# Spica_1_1.net
KiCad netlist of a schematic drawn in EAGLE
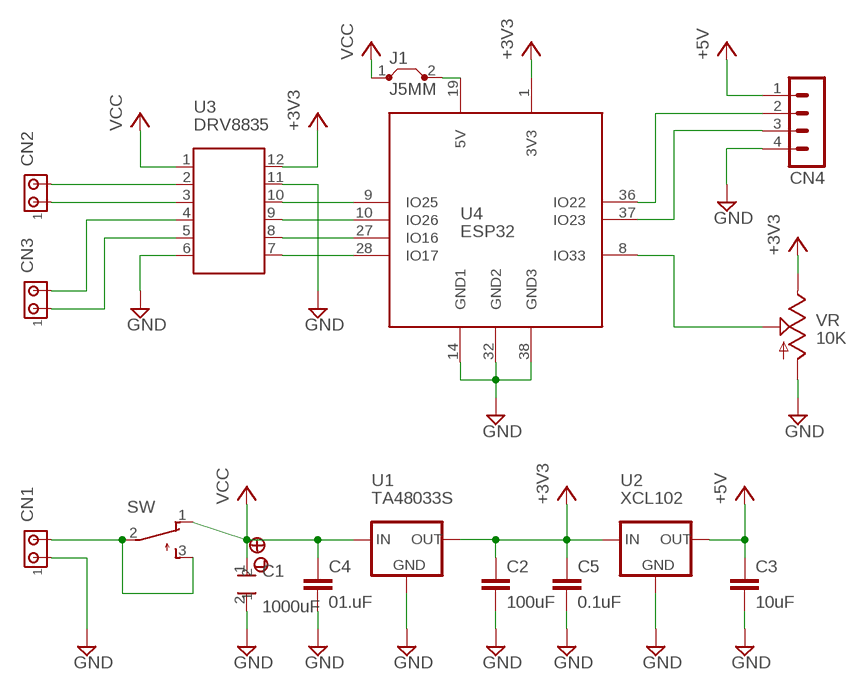
[diagram p0: schematic, sheet 1]

(export (version "E")
  (design (tool "Eeschema 10.0.6"))
  (components
    (comp (ref "C1")
      (value "1000uF")
      (footprint "eagle-import:ELECTROLYTIC_CAPACITOR_LARGE")
      (libsource (lib "eagle-import") (part "ELECTROLYTIC_CAPACITOR_LARGE"))
    )
    (comp (ref "C2")
      (value "100uF")
      (footprint "eagle-import:C2.5-5")
      (libsource (lib "eagle-import") (part "C2.5/5"))
    )
    (comp (ref "C3")
      (value "10uF")
      (footprint "eagle-import:C2.5-5")
      (libsource (lib "eagle-import") (part "C2.5/5"))
    )
    (comp (ref "C4")
      (value "01.uF")
      (footprint "eagle-import:C2.5-2")
      (libsource (lib "eagle-import") (part "C2.5/2"))
    )
    (comp (ref "C5")
      (value "0.1uF")
      (footprint "eagle-import:C2.5-2")
      (libsource (lib "eagle-import") (part "C2.5/2"))
    )
    (comp (ref "CN1")
      (value "MTA02-100")
      (footprint "eagle-import:10X02MTA")
      (libsource (lib "eagle-import") (part "MTA02-100"))
    )
    (comp (ref "CN2")
      (value "MTA02-100")
      (footprint "eagle-import:10X02MTA")
      (libsource (lib "eagle-import") (part "MTA02-100"))
    )
    (comp (ref "CN3")
      (value "MTA02-100")
      (footprint "eagle-import:10X02MTA")
      (libsource (lib "eagle-import") (part "MTA02-100"))
    )
    (comp (ref "CN4")
      (value "MA04-1")
      (footprint "eagle-import:MA04-1")
      (libsource (lib "eagle-import") (part "MA04-1"))
    )
    (comp (ref "J1")
      (value "J5MM")
      (footprint "eagle-import:05")
      (libsource (lib "eagle-import") (part "J5MM"))
    )
    (comp (ref "SW")
      (value "TL32PO")
      (footprint "eagle-import:TL3XPO")
      (libsource (lib "eagle-import") (part "TL32PO"))
    )
    (comp (ref "U1")
      (value "TA48033S")
      (footprint "eagle-import:78XXS")
      (libsource (lib "eagle-import") (part "78XXS"))
    )
    (comp (ref "U2")
      (value "XCL102")
      (footprint "eagle-import:78XXS")
      (libsource (lib "eagle-import") (part "78XXS"))
    )
    (comp (ref "U3")
      (value "DRV8835")
      (footprint "eagle-import:DRV8835")
      (libsource (lib "eagle-import") (part "DRV8835"))
    )
    (comp (ref "U4")
      (value "ESP32")
      (footprint "eagle-import:ESP32")
      (libsource (lib "eagle-import") (part "ESP32"))
    )
    (comp (ref "VR")
      (value "10K")
      (footprint "eagle-import:CA6V")
      (libsource (lib "eagle-import") (part "TRIM_US-CA6V"))
    )
  )
  (nets
    (net (code "1") (name "+3V3") (class "Default")
      (node (ref "C2") (pin "1") (pinfunction "1_1") (pintype "passive"))
      (node (ref "C5") (pin "1") (pinfunction "1_1") (pintype "passive"))
      (node (ref "U1") (pin "OUT") (pinfunction "OUT_OUT") (pintype "passive"))
      (node (ref "U2") (pin "IN") (pinfunction "IN_IN") (pintype "input"))
      (node (ref "U3") (pin "12") (pinfunction "12_12") (pintype "bidirectional"))
      (node (ref "U4") (pin "1") (pinfunction "3V3_1") (pintype "bidirectional"))
      (node (ref "VR") (pin "E") (pinfunction "E_E") (pintype "passive"))
    )
    (net (code "2") (name "+5V") (class "Default")
      (node (ref "C3") (pin "1") (pinfunction "1_1") (pintype "passive"))
      (node (ref "CN4") (pin "1") (pinfunction "1_1") (pintype "passive"))
      (node (ref "U2") (pin "OUT") (pinfunction "OUT_OUT") (pintype "passive"))
    )
    (net (code "3") (name "GND") (class "Default")
      (node (ref "C1") (pin "2") (pinfunction "2_2") (pintype "bidirectional"))
      (node (ref "C2") (pin "2") (pinfunction "2_2") (pintype "passive"))
      (node (ref "C3") (pin "2") (pinfunction "2_2") (pintype "passive"))
      (node (ref "C4") (pin "2") (pinfunction "2_2") (pintype "passive"))
      (node (ref "C5") (pin "2") (pinfunction "2_2") (pintype "passive"))
      (node (ref "CN1") (pin "1") (pinfunction "1_1") (pintype "passive"))
      (node (ref "CN4") (pin "4") (pinfunction "4_4") (pintype "passive"))
      (node (ref "U1") (pin "GND") (pinfunction "GND_GND") (pintype "input"))
      (node (ref "U2") (pin "GND") (pinfunction "GND_GND") (pintype "input"))
      (node (ref "U3") (pin "11") (pinfunction "11_11") (pintype "bidirectional"))
      (node (ref "U3") (pin "6") (pinfunction "6_6") (pintype "bidirectional"))
      (node (ref "U4") (pin "14") (pinfunction "GND1_14") (pintype "bidirectional"))
      (node (ref "U4") (pin "32") (pinfunction "GND2_32") (pintype "bidirectional"))
      (node (ref "U4") (pin "38") (pinfunction "GND3_38") (pintype "bidirectional"))
      (node (ref "VR") (pin "A") (pinfunction "A_A") (pintype "passive"))
    )
    (net (code "4") (name "Net-(CN2-Pad1)") (class "Default")
      (node (ref "CN2") (pin "1") (pinfunction "1_1") (pintype "passive"))
      (node (ref "U3") (pin "3") (pinfunction "3_3") (pintype "bidirectional"))
    )
    (net (code "5") (name "Net-(CN2-Pad2)") (class "Default")
      (node (ref "CN2") (pin "2") (pinfunction "2_2") (pintype "passive"))
      (node (ref "U3") (pin "2") (pinfunction "2_2") (pintype "bidirectional"))
    )
    (net (code "6") (name "Net-(CN3-Pad1)") (class "Default")
      (node (ref "CN3") (pin "1") (pinfunction "1_1") (pintype "passive"))
      (node (ref "U3") (pin "5") (pinfunction "5_5") (pintype "bidirectional"))
    )
    (net (code "7") (name "Net-(CN3-Pad2)") (class "Default")
      (node (ref "CN3") (pin "2") (pinfunction "2_2") (pintype "passive"))
      (node (ref "U3") (pin "4") (pinfunction "4_4") (pintype "bidirectional"))
    )
    (net (code "8") (name "Net-(SW-P)") (class "Default")
      (node (ref "CN1") (pin "2") (pinfunction "2_2") (pintype "passive"))
      (node (ref "SW") (pin "2") (pinfunction "P_2") (pintype "passive"))
      (node (ref "SW") (pin "3") (pinfunction "S_3") (pintype "passive"))
    )
    (net (code "9") (name "Net-(U4-5V)") (class "Default")
      (node (ref "J1") (pin "2") (pinfunction "2_2") (pintype "passive"))
      (node (ref "U4") (pin "19") (pinfunction "5V_19") (pintype "bidirectional"))
    )
    (net (code "10") (name "Net-(U4-IO16)") (class "Default")
      (node (ref "U3") (pin "8") (pinfunction "8_8") (pintype "bidirectional"))
      (node (ref "U4") (pin "27") (pinfunction "IO16_27") (pintype "bidirectional"))
    )
    (net (code "11") (name "Net-(U4-IO17)") (class "Default")
      (node (ref "U3") (pin "7") (pinfunction "7_7") (pintype "bidirectional"))
      (node (ref "U4") (pin "28") (pinfunction "IO17_28") (pintype "bidirectional"))
    )
    (net (code "12") (name "Net-(U4-IO22)") (class "Default")
      (node (ref "CN4") (pin "2") (pinfunction "2_2") (pintype "passive"))
      (node (ref "U4") (pin "36") (pinfunction "IO22_36") (pintype "bidirectional"))
    )
    (net (code "13") (name "Net-(U4-IO23)") (class "Default")
      (node (ref "CN4") (pin "3") (pinfunction "3_3") (pintype "passive"))
      (node (ref "U4") (pin "37") (pinfunction "IO23_37") (pintype "bidirectional"))
    )
    (net (code "14") (name "Net-(U4-IO25)") (class "Default")
      (node (ref "U3") (pin "10") (pinfunction "10_10") (pintype "bidirectional"))
      (node (ref "U4") (pin "9") (pinfunction "IO25_9") (pintype "bidirectional"))
    )
    (net (code "15") (name "Net-(U4-IO26)") (class "Default")
      (node (ref "U3") (pin "9") (pinfunction "9_9") (pintype "bidirectional"))
      (node (ref "U4") (pin "10") (pinfunction "IO26_10") (pintype "bidirectional"))
    )
    (net (code "16") (name "Net-(U4-IO33)") (class "Default")
      (node (ref "U4") (pin "8") (pinfunction "IO33_8") (pintype "bidirectional"))
      (node (ref "VR") (pin "S") (pinfunction "S_S") (pintype "passive"))
    )
    (net (code "17") (name "VCC") (class "Default")
      (node (ref "C1") (pin "1") (pinfunction "1_1") (pintype "bidirectional"))
      (node (ref "C4") (pin "1") (pinfunction "1_1") (pintype "passive"))
      (node (ref "J1") (pin "1") (pinfunction "1_1") (pintype "passive"))
      (node (ref "SW") (pin "1") (pinfunction "O_1") (pintype "passive"))
      (node (ref "U1") (pin "IN") (pinfunction "IN_IN") (pintype "input"))
      (node (ref "U3") (pin "1") (pinfunction "1_1") (pintype "bidirectional"))
    )
  )
)
